# CRAFT_Current_Sense_Circuit_AJeffersonRe.net
KiCad netlist of a schematic drawn in Altium Designer
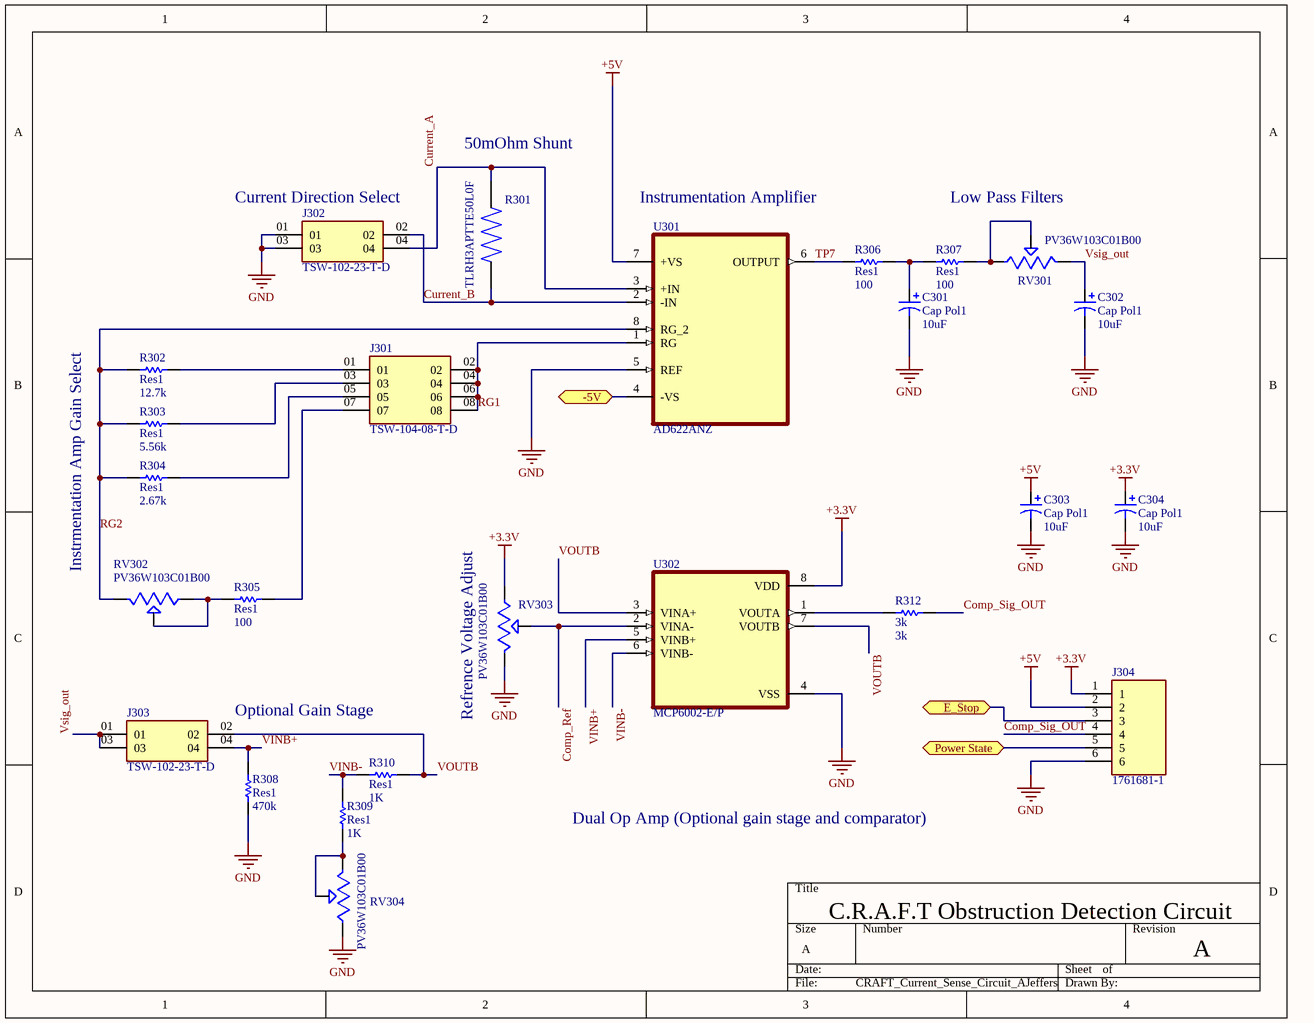
[diagram p0: CRAFT_Current_Sense_Circuit_AJeffersonRev2.SchDoc]

(export (version "E")
  (design (tool "Eeschema 10.0.6"))
  (components
    (comp (ref "C301")
      (value "Cap Pol1")
      (footprint "CAPPRD250W50D630H1120")
      (description "Polarized Capacitor (Radial)")
      (fields (field (name "ALTIUM_VALUE") "10uF") (field (name "PUBLISHER") "Altium Limited"))
      (libsource (lib "Miscellaneous Devices") (part "Cap Pol1"))
    )
    (comp (ref "C302")
      (value "Cap Pol1")
      (footprint "CAPPRD250W50D630H1120")
      (description "Polarized Capacitor (Radial)")
      (fields (field (name "ALTIUM_VALUE") "10uF") (field (name "PUBLISHER") "Altium Limited"))
      (libsource (lib "Miscellaneous Devices") (part "Cap Pol1"))
    )
    (comp (ref "C303")
      (value "Cap Pol1")
      (footprint "CAPPRD250W50D630H1120")
      (description "Polarized Capacitor (Radial)")
      (fields (field (name "ALTIUM_VALUE") "10uF") (field (name "PUBLISHER") "Altium Limited"))
      (libsource (lib "Miscellaneous Devices") (part "Cap Pol1"))
    )
    (comp (ref "C304")
      (value "Cap Pol1")
      (footprint "CAPPRD250W50D630H1120")
      (description "Polarized Capacitor (Radial)")
      (fields (field (name "ALTIUM_VALUE") "10uF") (field (name "PUBLISHER") "Altium Limited"))
      (libsource (lib "Miscellaneous Devices") (part "Cap Pol1"))
    )
    (comp (ref "J301")
      (value "TSW-104-08-T-D")
      (footprint "SAMTEC_TSW-104-08-T-D")
      (libsource (lib "TSW-104-08-T-D") (part "TSW-104-08-T-D"))
    )
    (comp (ref "J302")
      (value "TSW-102-23-T-D")
      (footprint "SAMTEC_TSW-102-23-T-D")
      (libsource (lib "TSW-102-23-T-D") (part "TSW-102-23-T-D"))
    )
    (comp (ref "J303")
      (value "TSW-102-23-T-D")
      (footprint "SAMTEC_TSW-102-23-T-D")
      (libsource (lib "TSW-102-23-T-D") (part "TSW-102-23-T-D"))
    )
    (comp (ref "J304")
      (value "1761681-1")
      (footprint "TE_1761681-1")
      (fields (field (name "MF") "{'manufacturer': 'TE Connectivity'}"))
      (libsource (lib "1761681-1") (part "1761681-1"))
    )
    (comp (ref "R301")
      (value "TLRH3APTTE50L0F")
      (footprint "RESC6332X70N")
      (description "Res Metal Plate 2512 0.047 Ohm 1% 4W Â±50ppm/C Pad SMD Automotive T/R")
      (fields (field (name "MP") "TLRH3APTTE47L0F"))
      (libsource (lib "TLRH3APTTE47L0F") (part "TLRH3APTTE47L0F"))
    )
    (comp (ref "R302")
      (value "Res1")
      (footprint "AXIAL-0.3")
      (description "Resistor")
      (fields (field (name "ALTIUM_VALUE") "12.7k") (field (name "PUBLISHER") "Altium Limited"))
      (libsource (lib "Miscellaneous Devices") (part "Res1"))
    )
    (comp (ref "R303")
      (value "Res1")
      (footprint "AXIAL-0.3")
      (description "Resistor")
      (fields (field (name "ALTIUM_VALUE") "5.56k") (field (name "PUBLISHER") "Altium Limited"))
      (libsource (lib "Miscellaneous Devices") (part "Res1"))
    )
    (comp (ref "R304")
      (value "Res1")
      (footprint "AXIAL-0.3")
      (description "Resistor")
      (fields (field (name "ALTIUM_VALUE") "2.67k") (field (name "PUBLISHER") "Altium Limited"))
      (libsource (lib "Miscellaneous Devices") (part "Res1"))
    )
    (comp (ref "R305")
      (value "Res1")
      (footprint "AXIAL-0.3")
      (description "Resistor")
      (fields (field (name "ALTIUM_VALUE") "100") (field (name "PUBLISHER") "Altium Limited"))
      (libsource (lib "Miscellaneous Devices") (part "Res1"))
    )
    (comp (ref "R306")
      (value "Res1")
      (footprint "AXIAL-0.3")
      (description "Resistor")
      (fields (field (name "ALTIUM_VALUE") "100") (field (name "PUBLISHER") "Altium Limited"))
      (libsource (lib "Miscellaneous Devices") (part "Res1"))
    )
    (comp (ref "R307")
      (value "Res1")
      (footprint "AXIAL-0.3")
      (description "Resistor")
      (fields (field (name "ALTIUM_VALUE") "100") (field (name "PUBLISHER") "Altium Limited"))
      (libsource (lib "Miscellaneous Devices") (part "Res1"))
    )
    (comp (ref "R308")
      (value "Res1")
      (footprint "AXIAL-0.3")
      (description "Resistor")
      (fields (field (name "ALTIUM_VALUE") "470k") (field (name "PUBLISHER") "Altium Limited"))
      (libsource (lib "Miscellaneous Devices") (part "Res1"))
    )
    (comp (ref "R309")
      (value "Res1")
      (footprint "AXIAL-0.3")
      (description "Resistor")
      (fields (field (name "ALTIUM_VALUE") "1K") (field (name "PUBLISHER") "Altium Limited"))
      (libsource (lib "Miscellaneous Devices") (part "Res1"))
    )
    (comp (ref "R310")
      (value "Res1")
      (footprint "AXIAL-0.3")
      (description "Resistor")
      (fields (field (name "ALTIUM_VALUE") "1K") (field (name "PUBLISHER") "Altium Limited"))
      (libsource (lib "Miscellaneous Devices") (part "Res1"))
    )
    (comp (ref "R312")
      (value "3k")
      (footprint "AXIAL-0.3")
      (description "Resistor")
      (fields (field (name "ALTIUM_VALUE") "3k") (field (name "PUBLISHER") "Altium Limited"))
      (libsource (lib "Miscellaneous Devices") (part "Res1"))
    )
    (comp (ref "RV301")
      (value "PV36W103C01B00")
      (footprint "TRIM_PV36W103C01B00")
      (description "10 kOhms 0.5W, 1/2W PC Pins Through Hole Trimmer Potentiometer Cermet 25 Turn Top Adjustment")
      (fields (field (name "MF") "Bourns"))
      (libsource (lib "PV36W103C01B00") (part "PV36W103C01B00"))
    )
    (comp (ref "RV302")
      (value "PV36W103C01B00")
      (footprint "TRIM_PV36W103C01B00")
      (description "10 kOhms 0.5W, 1/2W PC Pins Through Hole Trimmer Potentiometer Cermet 25 Turn Top Adjustment")
      (fields (field (name "MF") "Bourns"))
      (libsource (lib "PV36W103C01B00") (part "PV36W103C01B00"))
    )
    (comp (ref "RV303")
      (value "PV36W103C01B00")
      (footprint "TRIM_PV36W103C01B00")
      (description "10 kOhms 0.5W, 1/2W PC Pins Through Hole Trimmer Potentiometer Cermet 25 Turn Top Adjustment")
      (fields (field (name "MF") "Bourns"))
      (libsource (lib "PV36W103C01B00") (part "PV36W103C01B00"))
    )
    (comp (ref "RV304")
      (value "PV36W103C01B00")
      (footprint "TRIM_PV36W103C01B00")
      (description "10 kOhms 0.5W, 1/2W PC Pins Through Hole Trimmer Potentiometer Cermet 25 Turn Top Adjustment")
      (fields (field (name "MF") "Bourns"))
      (libsource (lib "PV36W103C01B00") (part "PV36W103C01B00"))
    )
    (comp (ref "U301")
      (value "AD622ANZ")
      (footprint "DIP254P762X533-8")
      (description "Instrumentation Amplifier 1 Circuit 8-PDIP")
      (fields (field (name "MF") "Analog Devices"))
      (libsource (lib "AD622ANZ") (part "AD622ANZ"))
    )
    (comp (ref "U302")
      (value "MCP6002-E/P")
      (footprint "DIP787W46P254L927H533Q8")
      (description "General Purpose Amplifier 2 Circuit Rail-to-Rail 8-PDIP")
      (fields (field (name "MF") "Microchip"))
      (libsource (lib "MCP6002-E_P") (part "MCP6002-E/P"))
    )
  )
  (nets
    (net (code "1") (name "+3.3V") (class "Default")
      (node (ref "C304") (pin "1") (pinfunction "1_1") (pintype "passive"))
      (node (ref "J304") (pin "1") (pinfunction "1_1") (pintype "passive"))
      (node (ref "RV303") (pin "1") (pinfunction "1_1") (pintype "passive"))
      (node (ref "U302") (pin "8") (pinfunction "VDD_8") (pintype "power_in"))
    )
    (net (code "2") (name "+5V") (class "Default")
      (node (ref "C303") (pin "1") (pinfunction "1_1") (pintype "passive"))
      (node (ref "J304") (pin "2") (pinfunction "2_2") (pintype "passive"))
      (node (ref "U301") (pin "7") (pinfunction "+VS_7") (pintype "power_in"))
    )
    (net (code "3") (name "/-5V") (class "Default")
      (node (ref "U301") (pin "4") (pinfunction "-VS_4") (pintype "power_in"))
    )
    (net (code "4") (name "/Comp_Ref") (class "Default")
      (node (ref "RV303") (pin "2") (pinfunction "2_2") (pintype "passive"))
      (node (ref "U302") (pin "2") (pinfunction "VINA-_2") (pintype "input"))
    )
    (net (code "5") (name "/Comp_Sig_OUT") (class "Default")
      (node (ref "J304") (pin "4") (pinfunction "4_4") (pintype "passive"))
      (node (ref "R312") (pin "2") (pinfunction "2_2") (pintype "passive"))
    )
    (net (code "6") (name "/Current_A") (class "Default")
      (node (ref "J302") (pin "04") (pinfunction "04_04") (pintype "passive"))
      (node (ref "R301") (pin "2") (pinfunction "2_2") (pintype "passive"))
      (node (ref "U301") (pin "3") (pinfunction "+IN_3") (pintype "input"))
    )
    (net (code "7") (name "/Current_B") (class "Default")
      (node (ref "J302") (pin "02") (pinfunction "02_02") (pintype "passive"))
      (node (ref "R301") (pin "1") (pinfunction "1_1") (pintype "passive"))
      (node (ref "U301") (pin "2") (pinfunction "-IN_2") (pintype "input"))
    )
    (net (code "8") (name "/E_Stop") (class "Default")
      (node (ref "J304") (pin "3") (pinfunction "3_3") (pintype "passive"))
    )
    (net (code "9") (name "/Power State") (class "Default")
      (node (ref "J304") (pin "5") (pinfunction "5_5") (pintype "passive"))
    )
    (net (code "10") (name "/RG1") (class "Default")
      (node (ref "J301") (pin "02") (pinfunction "02_02") (pintype "passive"))
      (node (ref "J301") (pin "04") (pinfunction "04_04") (pintype "passive"))
      (node (ref "J301") (pin "06") (pinfunction "06_06") (pintype "passive"))
      (node (ref "J301") (pin "08") (pinfunction "08_08") (pintype "passive"))
      (node (ref "U301") (pin "1") (pinfunction "RG_1") (pintype "input"))
    )
    (net (code "11") (name "/RG2") (class "Default")
      (node (ref "R302") (pin "1") (pinfunction "1_1") (pintype "passive"))
      (node (ref "R303") (pin "1") (pinfunction "1_1") (pintype "passive"))
      (node (ref "R304") (pin "1") (pinfunction "1_1") (pintype "passive"))
      (node (ref "RV302") (pin "3") (pinfunction "3_3") (pintype "passive"))
      (node (ref "U301") (pin "8") (pinfunction "RG_2_8") (pintype "input"))
    )
    (net (code "12") (name "/TP7") (class "Default")
      (node (ref "R306") (pin "1") (pinfunction "1_1") (pintype "passive"))
      (node (ref "U301") (pin "6") (pinfunction "OUTPUT_6") (pintype "output"))
    )
    (net (code "13") (name "/VINB+") (class "Default")
      (node (ref "J303") (pin "04") (pinfunction "04_04") (pintype "passive"))
      (node (ref "R308") (pin "2") (pinfunction "2_2") (pintype "passive"))
      (node (ref "U302") (pin "5") (pinfunction "VINB+_5") (pintype "input"))
    )
    (net (code "14") (name "/VINB-") (class "Default")
      (node (ref "R309") (pin "2") (pinfunction "2_2") (pintype "passive"))
      (node (ref "R310") (pin "1") (pinfunction "1_1") (pintype "passive"))
      (node (ref "U302") (pin "6") (pinfunction "VINB-_6") (pintype "input"))
    )
    (net (code "15") (name "/VOUTB") (class "Default")
      (node (ref "J303") (pin "02") (pinfunction "02_02") (pintype "passive"))
      (node (ref "R310") (pin "2") (pinfunction "2_2") (pintype "passive"))
      (node (ref "U302") (pin "3") (pinfunction "VINA+_3") (pintype "input"))
      (node (ref "U302") (pin "7") (pinfunction "VOUTB_7") (pintype "output"))
    )
    (net (code "16") (name "/Vsig_out") (class "Default")
      (node (ref "C302") (pin "1") (pinfunction "1_1") (pintype "passive"))
      (node (ref "J303") (pin "01") (pinfunction "01_01") (pintype "passive"))
      (node (ref "J303") (pin "03") (pinfunction "03_03") (pintype "passive"))
      (node (ref "RV301") (pin "3") (pinfunction "3_3") (pintype "passive"))
    )
    (net (code "17") (name "GND") (class "Default")
      (node (ref "C301") (pin "2") (pinfunction "2_2") (pintype "passive"))
      (node (ref "C302") (pin "2") (pinfunction "2_2") (pintype "passive"))
      (node (ref "C303") (pin "2") (pinfunction "2_2") (pintype "passive"))
      (node (ref "C304") (pin "2") (pinfunction "2_2") (pintype "passive"))
      (node (ref "J302") (pin "01") (pinfunction "01_01") (pintype "passive"))
      (node (ref "J302") (pin "03") (pinfunction "03_03") (pintype "passive"))
      (node (ref "J304") (pin "6") (pinfunction "6_6") (pintype "passive"))
      (node (ref "R308") (pin "1") (pinfunction "1_1") (pintype "passive"))
      (node (ref "RV303") (pin "3") (pinfunction "3_3") (pintype "passive"))
      (node (ref "RV304") (pin "1") (pinfunction "1_1") (pintype "passive"))
      (node (ref "U301") (pin "5") (pinfunction "REF_5") (pintype "input"))
      (node (ref "U302") (pin "4") (pinfunction "VSS_4") (pintype "power_in"))
    )
    (net (code "18") (name "Net-(C301-Pad1)") (class "Default")
      (node (ref "C301") (pin "1") (pinfunction "1_1") (pintype "passive"))
      (node (ref "R306") (pin "2") (pinfunction "2_2") (pintype "passive"))
      (node (ref "R307") (pin "1") (pinfunction "1_1") (pintype "passive"))
    )
    (net (code "19") (name "Net-(J301-Pad01)") (class "Default")
      (node (ref "J301") (pin "01") (pinfunction "01_01") (pintype "passive"))
      (node (ref "R302") (pin "2") (pinfunction "2_2") (pintype "passive"))
    )
    (net (code "20") (name "Net-(J301-Pad03)") (class "Default")
      (node (ref "J301") (pin "03") (pinfunction "03_03") (pintype "passive"))
      (node (ref "R303") (pin "2") (pinfunction "2_2") (pintype "passive"))
    )
    (net (code "21") (name "Net-(J301-Pad05)") (class "Default")
      (node (ref "J301") (pin "05") (pinfunction "05_05") (pintype "passive"))
      (node (ref "R304") (pin "2") (pinfunction "2_2") (pintype "passive"))
    )
    (net (code "22") (name "Net-(J301-Pad07)") (class "Default")
      (node (ref "J301") (pin "07") (pinfunction "07_07") (pintype "passive"))
      (node (ref "R305") (pin "2") (pinfunction "2_2") (pintype "passive"))
    )
    (net (code "23") (name "Net-(R305-Pad1)") (class "Default")
      (node (ref "R305") (pin "1") (pinfunction "1_1") (pintype "passive"))
      (node (ref "RV302") (pin "1") (pinfunction "1_1") (pintype "passive"))
      (node (ref "RV302") (pin "2") (pinfunction "2_2") (pintype "passive"))
    )
    (net (code "24") (name "Net-(R307-Pad2)") (class "Default")
      (node (ref "R307") (pin "2") (pinfunction "2_2") (pintype "passive"))
      (node (ref "RV301") (pin "1") (pinfunction "1_1") (pintype "passive"))
      (node (ref "RV301") (pin "2") (pinfunction "2_2") (pintype "passive"))
    )
    (net (code "25") (name "Net-(R309-Pad1)") (class "Default")
      (node (ref "R309") (pin "1") (pinfunction "1_1") (pintype "passive"))
      (node (ref "RV304") (pin "2") (pinfunction "2_2") (pintype "passive"))
      (node (ref "RV304") (pin "3") (pinfunction "3_3") (pintype "passive"))
    )
    (net (code "26") (name "Net-(U302-VOUTA)") (class "Default")
      (node (ref "R312") (pin "1") (pinfunction "1_1") (pintype "passive"))
      (node (ref "U302") (pin "1") (pinfunction "VOUTA_1") (pintype "output"))
    )
  )
)
